# GridThumbs.net
KiCad netlist of a schematic drawn in EAGLE
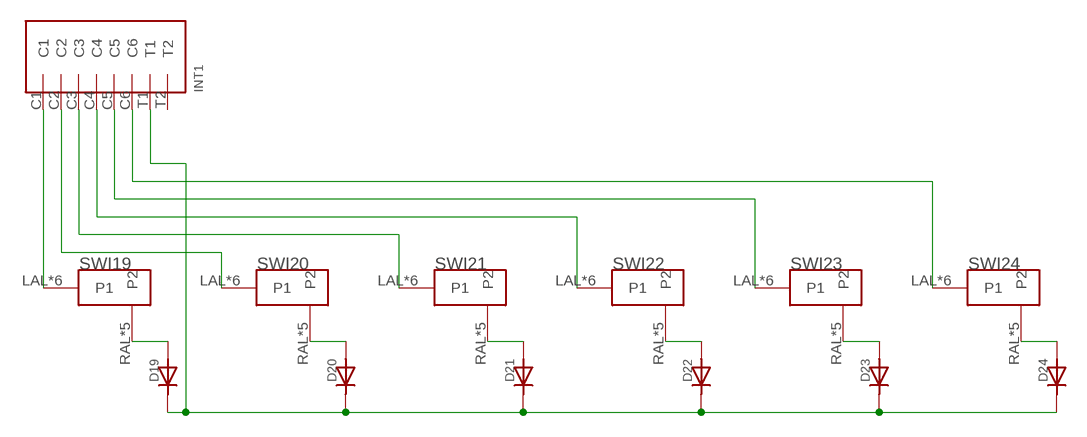
[diagram p0: schematic, sheet 1]

(export (version "E")
  (design (tool "Eeschema 10.0.6"))
  (components
    (comp (ref "D19")
      (value "DIODE")
      (footprint "eagle-import:DIODE_COMBO")
      (libsource (lib "eagle-import") (part "DIODE"))
    )
    (comp (ref "D20")
      (value "DIODE")
      (footprint "eagle-import:DIODE_COMBO")
      (libsource (lib "eagle-import") (part "DIODE"))
    )
    (comp (ref "D21")
      (value "DIODE")
      (footprint "eagle-import:DIODE_COMBO")
      (libsource (lib "eagle-import") (part "DIODE"))
    )
    (comp (ref "D22")
      (value "DIODE")
      (footprint "eagle-import:DIODE_COMBO")
      (libsource (lib "eagle-import") (part "DIODE"))
    )
    (comp (ref "D23")
      (value "DIODE")
      (footprint "eagle-import:DIODE_COMBO")
      (libsource (lib "eagle-import") (part "DIODE"))
    )
    (comp (ref "D24")
      (value "DIODE")
      (footprint "eagle-import:DIODE_COMBO")
      (libsource (lib "eagle-import") (part "DIODE"))
    )
    (comp (ref "INT1")
      (value "INTRCNNT4X2")
      (footprint "eagle-import:INTRRIBBON")
      (libsource (lib "eagle-import") (part "INTRCNNT4X2"))
    )
    (comp (ref "SWI19")
      (value "MX/ALPSDOUBLESIDED")
      (footprint "eagle-import:DOUBLED_MX_ALPS")
      (libsource (lib "eagle-import") (part "MX/ALPSDOUBLESIDED"))
    )
    (comp (ref "SWI20")
      (value "MX/ALPSDOUBLESIDED")
      (footprint "eagle-import:DOUBLED_MX_ALPS")
      (libsource (lib "eagle-import") (part "MX/ALPSDOUBLESIDED"))
    )
    (comp (ref "SWI21")
      (value "MX/ALPSDOUBLESIDED")
      (footprint "eagle-import:DOUBLED_MX_ALPS")
      (libsource (lib "eagle-import") (part "MX/ALPSDOUBLESIDED"))
    )
    (comp (ref "SWI22")
      (value "MX/ALPSDOUBLESIDED")
      (footprint "eagle-import:DOUBLED_MX_ALPS")
      (libsource (lib "eagle-import") (part "MX/ALPSDOUBLESIDED"))
    )
    (comp (ref "SWI23")
      (value "MX/ALPSDOUBLESIDED")
      (footprint "eagle-import:DOUBLED_MX_ALPS")
      (libsource (lib "eagle-import") (part "MX/ALPSDOUBLESIDED"))
    )
    (comp (ref "SWI24")
      (value "MX/ALPSDOUBLESIDED")
      (footprint "eagle-import:DOUBLED_MX_ALPS")
      (libsource (lib "eagle-import") (part "MX/ALPSDOUBLESIDED"))
    )
  )
  (nets
    (net (code "1") (name "Net-(D19-AN-PadANOSB)") (class "Default")
      (node (ref "D19") (pin "ANOSB") (pinfunction "AN_ANOSB") (pintype "bidirectional"))
      (node (ref "D19") (pin "ANOST") (pinfunction "AN_ANOST") (pintype "bidirectional"))
      (node (ref "D19") (pin "ANOT") (pinfunction "AN_ANOT") (pintype "bidirectional"))
      (node (ref "SWI19") (pin "RAL") (pinfunction "P2_RAL") (pintype "bidirectional"))
      (node (ref "SWI19") (pin "RAR") (pinfunction "P2_RAR") (pintype "bidirectional"))
      (node (ref "SWI19") (pin "RCL") (pinfunction "P2_RCL") (pintype "bidirectional"))
      (node (ref "SWI19") (pin "RCR") (pinfunction "P2_RCR") (pintype "bidirectional"))
      (node (ref "SWI19") (pin "RLMID") (pinfunction "P2_RLMID") (pintype "bidirectional"))
    )
    (net (code "2") (name "Net-(D19-CAT-PadCATSB)") (class "Default")
      (node (ref "D19") (pin "CATSB") (pinfunction "CAT_CATSB") (pintype "bidirectional"))
      (node (ref "D19") (pin "CATST") (pinfunction "CAT_CATST") (pintype "bidirectional"))
      (node (ref "D19") (pin "CATT") (pinfunction "CAT_CATT") (pintype "bidirectional"))
      (node (ref "D20") (pin "CATSB") (pinfunction "CAT_CATSB") (pintype "bidirectional"))
      (node (ref "D20") (pin "CATST") (pinfunction "CAT_CATST") (pintype "bidirectional"))
      (node (ref "D20") (pin "CATT") (pinfunction "CAT_CATT") (pintype "bidirectional"))
      (node (ref "D21") (pin "CATSB") (pinfunction "CAT_CATSB") (pintype "bidirectional"))
      (node (ref "D21") (pin "CATST") (pinfunction "CAT_CATST") (pintype "bidirectional"))
      (node (ref "D21") (pin "CATT") (pinfunction "CAT_CATT") (pintype "bidirectional"))
      (node (ref "D22") (pin "CATSB") (pinfunction "CAT_CATSB") (pintype "bidirectional"))
      (node (ref "D22") (pin "CATST") (pinfunction "CAT_CATST") (pintype "bidirectional"))
      (node (ref "D22") (pin "CATT") (pinfunction "CAT_CATT") (pintype "bidirectional"))
      (node (ref "D23") (pin "CATSB") (pinfunction "CAT_CATSB") (pintype "bidirectional"))
      (node (ref "D23") (pin "CATST") (pinfunction "CAT_CATST") (pintype "bidirectional"))
      (node (ref "D23") (pin "CATT") (pinfunction "CAT_CATT") (pintype "bidirectional"))
      (node (ref "D24") (pin "CATSB") (pinfunction "CAT_CATSB") (pintype "bidirectional"))
      (node (ref "D24") (pin "CATST") (pinfunction "CAT_CATST") (pintype "bidirectional"))
      (node (ref "D24") (pin "CATT") (pinfunction "CAT_CATT") (pintype "bidirectional"))
      (node (ref "INT1") (pin "T1") (pinfunction "T1_T1") (pintype "bidirectional"))
    )
    (net (code "3") (name "Net-(D20-AN-PadANOSB)") (class "Default")
      (node (ref "D20") (pin "ANOSB") (pinfunction "AN_ANOSB") (pintype "bidirectional"))
      (node (ref "D20") (pin "ANOST") (pinfunction "AN_ANOST") (pintype "bidirectional"))
      (node (ref "D20") (pin "ANOT") (pinfunction "AN_ANOT") (pintype "bidirectional"))
      (node (ref "SWI20") (pin "RAL") (pinfunction "P2_RAL") (pintype "bidirectional"))
      (node (ref "SWI20") (pin "RAR") (pinfunction "P2_RAR") (pintype "bidirectional"))
      (node (ref "SWI20") (pin "RCL") (pinfunction "P2_RCL") (pintype "bidirectional"))
      (node (ref "SWI20") (pin "RCR") (pinfunction "P2_RCR") (pintype "bidirectional"))
      (node (ref "SWI20") (pin "RLMID") (pinfunction "P2_RLMID") (pintype "bidirectional"))
    )
    (net (code "4") (name "Net-(D21-AN-PadANOSB)") (class "Default")
      (node (ref "D21") (pin "ANOSB") (pinfunction "AN_ANOSB") (pintype "bidirectional"))
      (node (ref "D21") (pin "ANOST") (pinfunction "AN_ANOST") (pintype "bidirectional"))
      (node (ref "D21") (pin "ANOT") (pinfunction "AN_ANOT") (pintype "bidirectional"))
      (node (ref "SWI21") (pin "RAL") (pinfunction "P2_RAL") (pintype "bidirectional"))
      (node (ref "SWI21") (pin "RAR") (pinfunction "P2_RAR") (pintype "bidirectional"))
      (node (ref "SWI21") (pin "RCL") (pinfunction "P2_RCL") (pintype "bidirectional"))
      (node (ref "SWI21") (pin "RCR") (pinfunction "P2_RCR") (pintype "bidirectional"))
      (node (ref "SWI21") (pin "RLMID") (pinfunction "P2_RLMID") (pintype "bidirectional"))
    )
    (net (code "5") (name "Net-(D22-AN-PadANOSB)") (class "Default")
      (node (ref "D22") (pin "ANOSB") (pinfunction "AN_ANOSB") (pintype "bidirectional"))
      (node (ref "D22") (pin "ANOST") (pinfunction "AN_ANOST") (pintype "bidirectional"))
      (node (ref "D22") (pin "ANOT") (pinfunction "AN_ANOT") (pintype "bidirectional"))
      (node (ref "SWI22") (pin "RAL") (pinfunction "P2_RAL") (pintype "bidirectional"))
      (node (ref "SWI22") (pin "RAR") (pinfunction "P2_RAR") (pintype "bidirectional"))
      (node (ref "SWI22") (pin "RCL") (pinfunction "P2_RCL") (pintype "bidirectional"))
      (node (ref "SWI22") (pin "RCR") (pinfunction "P2_RCR") (pintype "bidirectional"))
      (node (ref "SWI22") (pin "RLMID") (pinfunction "P2_RLMID") (pintype "bidirectional"))
    )
    (net (code "6") (name "Net-(D23-AN-PadANOSB)") (class "Default")
      (node (ref "D23") (pin "ANOSB") (pinfunction "AN_ANOSB") (pintype "bidirectional"))
      (node (ref "D23") (pin "ANOST") (pinfunction "AN_ANOST") (pintype "bidirectional"))
      (node (ref "D23") (pin "ANOT") (pinfunction "AN_ANOT") (pintype "bidirectional"))
      (node (ref "SWI23") (pin "RAL") (pinfunction "P2_RAL") (pintype "bidirectional"))
      (node (ref "SWI23") (pin "RAR") (pinfunction "P2_RAR") (pintype "bidirectional"))
      (node (ref "SWI23") (pin "RCL") (pinfunction "P2_RCL") (pintype "bidirectional"))
      (node (ref "SWI23") (pin "RCR") (pinfunction "P2_RCR") (pintype "bidirectional"))
      (node (ref "SWI23") (pin "RLMID") (pinfunction "P2_RLMID") (pintype "bidirectional"))
    )
    (net (code "7") (name "Net-(D24-AN-PadANOSB)") (class "Default")
      (node (ref "D24") (pin "ANOSB") (pinfunction "AN_ANOSB") (pintype "bidirectional"))
      (node (ref "D24") (pin "ANOST") (pinfunction "AN_ANOST") (pintype "bidirectional"))
      (node (ref "D24") (pin "ANOT") (pinfunction "AN_ANOT") (pintype "bidirectional"))
      (node (ref "SWI24") (pin "RAL") (pinfunction "P2_RAL") (pintype "bidirectional"))
      (node (ref "SWI24") (pin "RAR") (pinfunction "P2_RAR") (pintype "bidirectional"))
      (node (ref "SWI24") (pin "RCL") (pinfunction "P2_RCL") (pintype "bidirectional"))
      (node (ref "SWI24") (pin "RCR") (pinfunction "P2_RCR") (pintype "bidirectional"))
      (node (ref "SWI24") (pin "RLMID") (pinfunction "P2_RLMID") (pintype "bidirectional"))
    )
    (net (code "8") (name "Net-(INT1-PadC1)") (class "Default")
      (node (ref "INT1") (pin "C1") (pinfunction "C1_C1") (pintype "bidirectional"))
      (node (ref "SWI19") (pin "LAL") (pinfunction "P1_LAL") (pintype "bidirectional"))
      (node (ref "SWI19") (pin "LAR") (pinfunction "P1_LAR") (pintype "bidirectional"))
      (node (ref "SWI19") (pin "LCL") (pinfunction "P1_LCL") (pintype "bidirectional"))
      (node (ref "SWI19") (pin "LCR") (pinfunction "P1_LCR") (pintype "bidirectional"))
      (node (ref "SWI19") (pin "LLP") (pinfunction "P1_LLP") (pintype "bidirectional"))
      (node (ref "SWI19") (pin "LRLP") (pinfunction "P1_LRLP") (pintype "bidirectional"))
    )
    (net (code "9") (name "Net-(INT1-PadC2)") (class "Default")
      (node (ref "INT1") (pin "C2") (pinfunction "C2_C2") (pintype "bidirectional"))
      (node (ref "SWI20") (pin "LAL") (pinfunction "P1_LAL") (pintype "bidirectional"))
      (node (ref "SWI20") (pin "LAR") (pinfunction "P1_LAR") (pintype "bidirectional"))
      (node (ref "SWI20") (pin "LCL") (pinfunction "P1_LCL") (pintype "bidirectional"))
      (node (ref "SWI20") (pin "LCR") (pinfunction "P1_LCR") (pintype "bidirectional"))
      (node (ref "SWI20") (pin "LLP") (pinfunction "P1_LLP") (pintype "bidirectional"))
      (node (ref "SWI20") (pin "LRLP") (pinfunction "P1_LRLP") (pintype "bidirectional"))
    )
    (net (code "10") (name "Net-(INT1-PadC3)") (class "Default")
      (node (ref "INT1") (pin "C3") (pinfunction "C3_C3") (pintype "bidirectional"))
      (node (ref "SWI21") (pin "LAL") (pinfunction "P1_LAL") (pintype "bidirectional"))
      (node (ref "SWI21") (pin "LAR") (pinfunction "P1_LAR") (pintype "bidirectional"))
      (node (ref "SWI21") (pin "LCL") (pinfunction "P1_LCL") (pintype "bidirectional"))
      (node (ref "SWI21") (pin "LCR") (pinfunction "P1_LCR") (pintype "bidirectional"))
      (node (ref "SWI21") (pin "LLP") (pinfunction "P1_LLP") (pintype "bidirectional"))
      (node (ref "SWI21") (pin "LRLP") (pinfunction "P1_LRLP") (pintype "bidirectional"))
    )
    (net (code "11") (name "Net-(INT1-PadC4)") (class "Default")
      (node (ref "INT1") (pin "C4") (pinfunction "C4_C4") (pintype "bidirectional"))
      (node (ref "SWI22") (pin "LAL") (pinfunction "P1_LAL") (pintype "bidirectional"))
      (node (ref "SWI22") (pin "LAR") (pinfunction "P1_LAR") (pintype "bidirectional"))
      (node (ref "SWI22") (pin "LCL") (pinfunction "P1_LCL") (pintype "bidirectional"))
      (node (ref "SWI22") (pin "LCR") (pinfunction "P1_LCR") (pintype "bidirectional"))
      (node (ref "SWI22") (pin "LLP") (pinfunction "P1_LLP") (pintype "bidirectional"))
      (node (ref "SWI22") (pin "LRLP") (pinfunction "P1_LRLP") (pintype "bidirectional"))
    )
    (net (code "12") (name "Net-(INT1-PadC5)") (class "Default")
      (node (ref "INT1") (pin "C5") (pinfunction "C5_C5") (pintype "bidirectional"))
      (node (ref "SWI23") (pin "LAL") (pinfunction "P1_LAL") (pintype "bidirectional"))
      (node (ref "SWI23") (pin "LAR") (pinfunction "P1_LAR") (pintype "bidirectional"))
      (node (ref "SWI23") (pin "LCL") (pinfunction "P1_LCL") (pintype "bidirectional"))
      (node (ref "SWI23") (pin "LCR") (pinfunction "P1_LCR") (pintype "bidirectional"))
      (node (ref "SWI23") (pin "LLP") (pinfunction "P1_LLP") (pintype "bidirectional"))
      (node (ref "SWI23") (pin "LRLP") (pinfunction "P1_LRLP") (pintype "bidirectional"))
    )
    (net (code "13") (name "Net-(INT1-PadC6)") (class "Default")
      (node (ref "INT1") (pin "C6") (pinfunction "C6_C6") (pintype "bidirectional"))
      (node (ref "SWI24") (pin "LAL") (pinfunction "P1_LAL") (pintype "bidirectional"))
      (node (ref "SWI24") (pin "LAR") (pinfunction "P1_LAR") (pintype "bidirectional"))
      (node (ref "SWI24") (pin "LCL") (pinfunction "P1_LCL") (pintype "bidirectional"))
      (node (ref "SWI24") (pin "LCR") (pinfunction "P1_LCR") (pintype "bidirectional"))
      (node (ref "SWI24") (pin "LLP") (pinfunction "P1_LLP") (pintype "bidirectional"))
      (node (ref "SWI24") (pin "LRLP") (pinfunction "P1_LRLP") (pintype "bidirectional"))
    )
    (net (code "14") (name "unconnected-(INT1-PadT2)") (class "Default")
      (node (ref "INT1") (pin "T2") (pinfunction "T2_T2") (pintype "bidirectional"))
    )
  )
)
